# prosismic.net
KiCad netlist of a schematic drawn in EAGLE
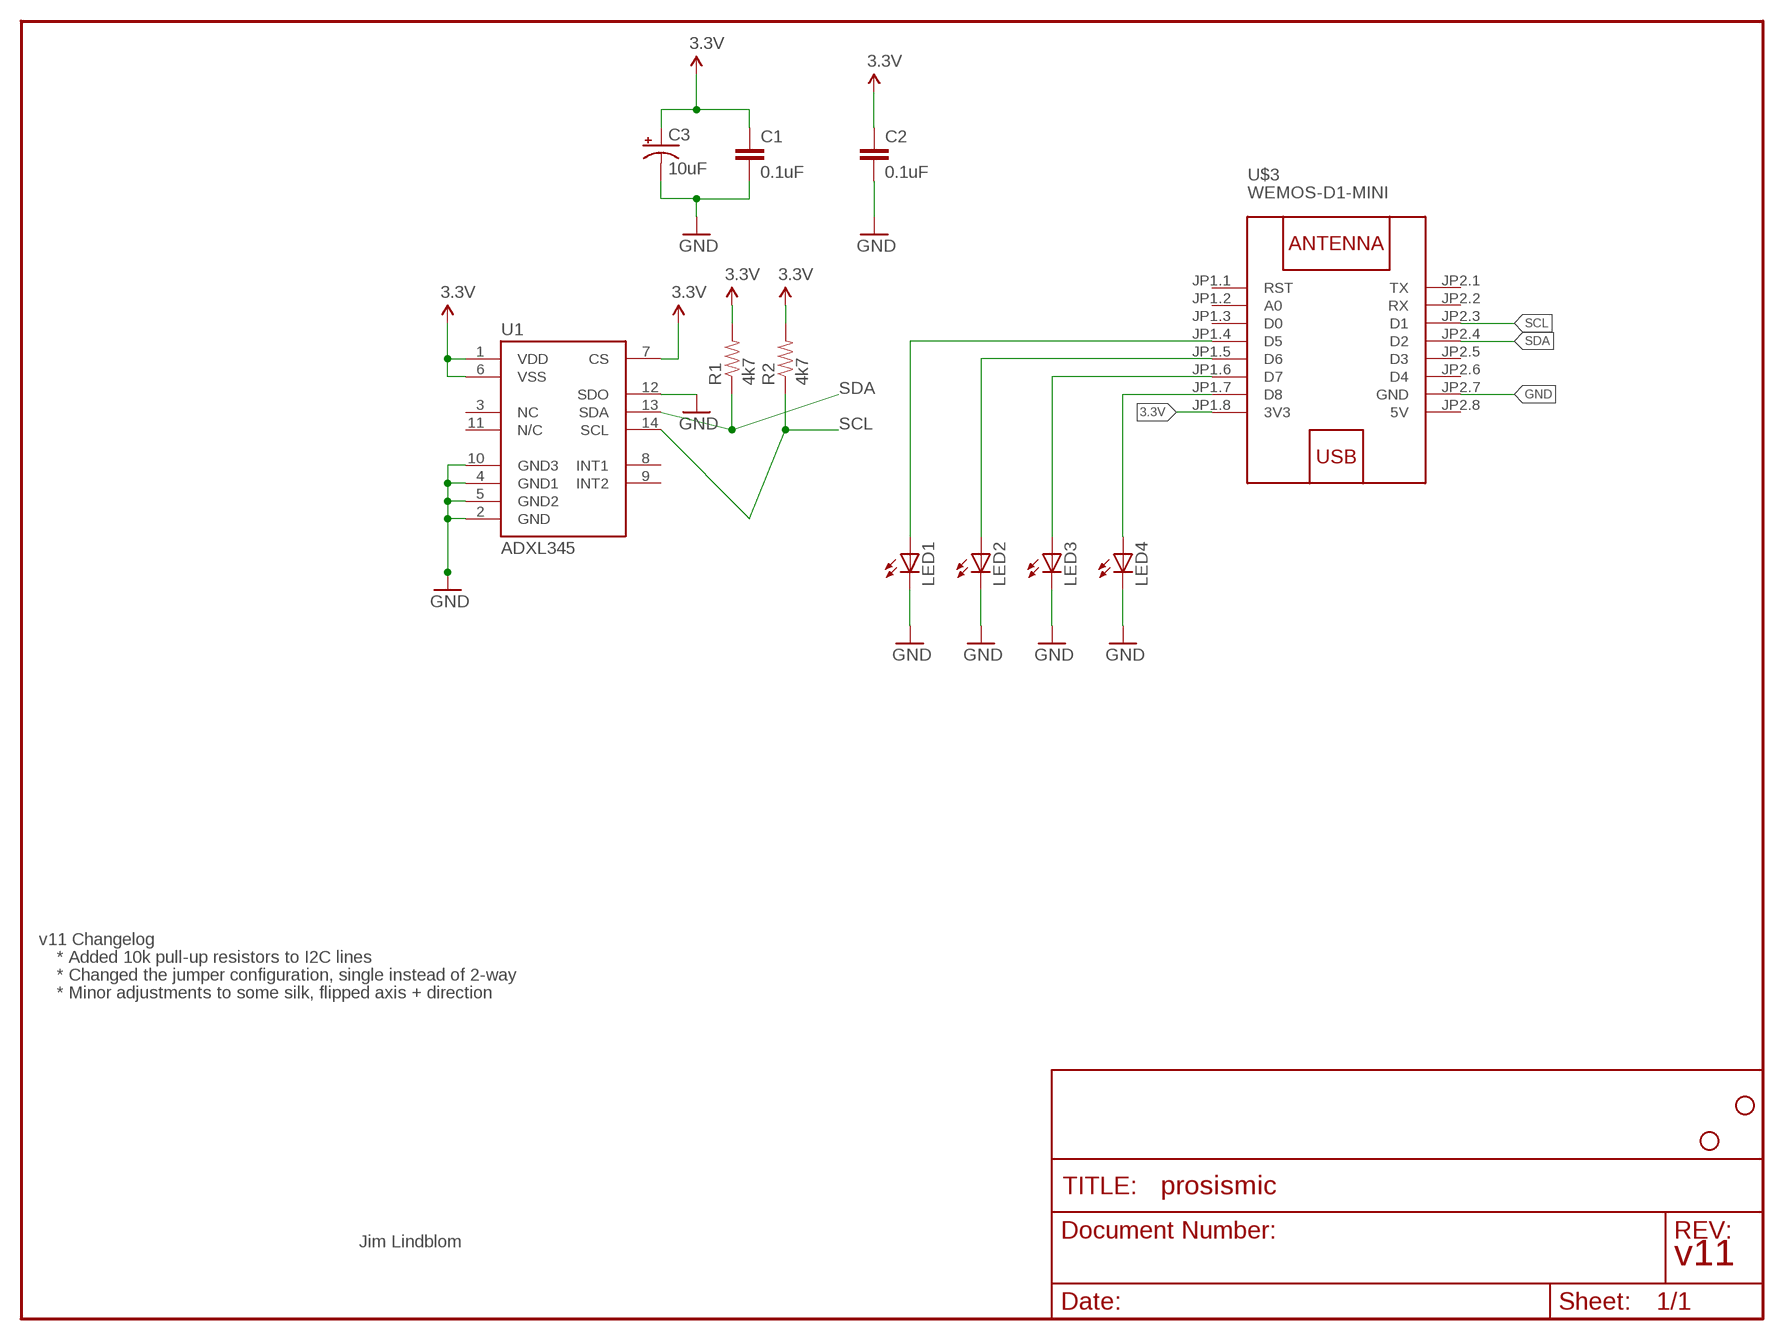
[diagram p0: schematic, sheet 1]

(export (version "E")
  (design (tool "Eeschema 10.0.6"))
  (components
    (comp (ref "C1")
      (value "0.1uF")
      (footprint "eagle-import:0402-CAP")
      (libsource (lib "eagle-import") (part "CAP0402-CAP"))
    )
    (comp (ref "C2")
      (value "0.1uF")
      (footprint "eagle-import:0402-CAP")
      (libsource (lib "eagle-import") (part "CAP0402-CAP"))
    )
    (comp (ref "C3")
      (value "10uF")
      (footprint "eagle-import:EIA3216")
      (libsource (lib "eagle-import") (part "CAP_POL1206"))
    )
    (comp (ref "JP3")
      (value "STAND-OFF")
      (footprint "eagle-import:STAND-OFF")
      (libsource (lib "eagle-import") (part "STAND-OFF"))
    )
    (comp (ref "JP4")
      (value "STAND-OFF")
      (footprint "eagle-import:STAND-OFF")
      (libsource (lib "eagle-import") (part "STAND-OFF"))
    )
    (comp (ref "LED1")
      (value "LED3MM")
      (footprint "eagle-import:LED3MM")
      (libsource (lib "eagle-import") (part "LED3MM"))
    )
    (comp (ref "LED2")
      (value "LED3MM")
      (footprint "eagle-import:LED3MM")
      (libsource (lib "eagle-import") (part "LED3MM"))
    )
    (comp (ref "LED3")
      (value "LED3MM")
      (footprint "eagle-import:LED3MM")
      (libsource (lib "eagle-import") (part "LED3MM"))
    )
    (comp (ref "LED4")
      (value "LED3MM")
      (footprint "eagle-import:LED3MM")
      (libsource (lib "eagle-import") (part "LED3MM"))
    )
    (comp (ref "R1")
      (value "4k7")
      (footprint "eagle-import:0402-RES")
      (libsource (lib "eagle-import") (part "RESISTOR0402-RES"))
    )
    (comp (ref "R2")
      (value "4k7")
      (footprint "eagle-import:0402-RES")
      (libsource (lib "eagle-import") (part "RESISTOR0402-RES"))
    )
    (comp (ref "U$3")
      (value "WEMOS-D1-MINI")
      (footprint "eagle-import:WEMOS-D1-MINI")
      (libsource (lib "eagle-import") (part "WEMOS-D1-MINI"))
    )
    (comp (ref "U1")
      (value "ADXL345")
      (footprint "eagle-import:LGA14")
      (libsource (lib "eagle-import") (part "ADXL345"))
    )
  )
  (nets
    (net (code "1") (name "/5V") (class "Default")
      (node (ref "U$3") (pin "JP2.8") (pinfunction "5V_JP2.8") (pintype "power_in"))
    )
    (net (code "2") (name "3.3V") (class "Default")
      (node (ref "C1") (pin "1") (pinfunction "1_1") (pintype "passive"))
      (node (ref "C2") (pin "1") (pinfunction "1_1") (pintype "passive"))
      (node (ref "C3") (pin "A") (pinfunction "+_A") (pintype "passive"))
      (node (ref "R1") (pin "2") (pinfunction "2_2") (pintype "passive"))
      (node (ref "R2") (pin "2") (pinfunction "2_2") (pintype "passive"))
      (node (ref "U$3") (pin "JP1.8") (pinfunction "3V3_JP1.8") (pintype "power_in"))
      (node (ref "U1") (pin "1") (pinfunction "VDD_1") (pintype "bidirectional"))
      (node (ref "U1") (pin "6") (pinfunction "VSS_6") (pintype "bidirectional"))
      (node (ref "U1") (pin "7") (pinfunction "CS_7") (pintype "bidirectional"))
    )
    (net (code "3") (name "GND") (class "Default")
      (node (ref "C1") (pin "2") (pinfunction "2_2") (pintype "passive"))
      (node (ref "C2") (pin "2") (pinfunction "2_2") (pintype "passive"))
      (node (ref "C3") (pin "C") (pinfunction "-_C") (pintype "passive"))
      (node (ref "LED1") (pin "K") (pinfunction "C_K") (pintype "passive"))
      (node (ref "LED2") (pin "K") (pinfunction "C_K") (pintype "passive"))
      (node (ref "LED3") (pin "K") (pinfunction "C_K") (pintype "passive"))
      (node (ref "LED4") (pin "K") (pinfunction "C_K") (pintype "passive"))
      (node (ref "U$3") (pin "JP2.7") (pinfunction "GND_JP2.7") (pintype "power_in"))
      (node (ref "U1") (pin "10") (pinfunction "GND3_10") (pintype "bidirectional"))
      (node (ref "U1") (pin "12") (pinfunction "SDO_12") (pintype "bidirectional"))
      (node (ref "U1") (pin "2") (pinfunction "GND_2") (pintype "bidirectional"))
      (node (ref "U1") (pin "4") (pinfunction "GND1_4") (pintype "bidirectional"))
      (node (ref "U1") (pin "5") (pinfunction "GND2_5") (pintype "bidirectional"))
    )
    (net (code "4") (name "Net-(U$3-D5)") (class "Default")
      (node (ref "LED1") (pin "A") (pinfunction "A_A") (pintype "passive"))
      (node (ref "U$3") (pin "JP1.4") (pinfunction "D5_JP1.4") (pintype "bidirectional"))
    )
    (net (code "5") (name "Net-(U$3-D6)") (class "Default")
      (node (ref "LED2") (pin "A") (pinfunction "A_A") (pintype "passive"))
      (node (ref "U$3") (pin "JP1.5") (pinfunction "D6_JP1.5") (pintype "bidirectional"))
    )
    (net (code "6") (name "Net-(U$3-D7)") (class "Default")
      (node (ref "LED3") (pin "A") (pinfunction "A_A") (pintype "passive"))
      (node (ref "U$3") (pin "JP1.6") (pinfunction "D7_JP1.6") (pintype "bidirectional"))
    )
    (net (code "7") (name "Net-(U$3-D8)") (class "Default")
      (node (ref "LED4") (pin "A") (pinfunction "A_A") (pintype "passive"))
      (node (ref "U$3") (pin "JP1.7") (pinfunction "D8_JP1.7") (pintype "bidirectional"))
    )
    (net (code "8") (name "SCL") (class "Default")
      (node (ref "R2") (pin "1") (pinfunction "1_1") (pintype "passive"))
      (node (ref "U$3") (pin "JP2.3") (pinfunction "D1_JP2.3") (pintype "bidirectional"))
      (node (ref "U1") (pin "14") (pinfunction "SCL_14") (pintype "bidirectional"))
    )
    (net (code "9") (name "SDA") (class "Default")
      (node (ref "R1") (pin "1") (pinfunction "1_1") (pintype "passive"))
      (node (ref "U$3") (pin "JP2.4") (pinfunction "D2_JP2.4") (pintype "bidirectional"))
      (node (ref "U1") (pin "13") (pinfunction "SDA_13") (pintype "bidirectional"))
    )
    (net (code "10") (name "unconnected-(U$3-A0-PadJP1.2)") (class "Default")
      (node (ref "U$3") (pin "JP1.2") (pinfunction "A0_JP1.2") (pintype "bidirectional"))
    )
    (net (code "11") (name "unconnected-(U$3-D0-PadJP1.3)") (class "Default")
      (node (ref "U$3") (pin "JP1.3") (pinfunction "D0_JP1.3") (pintype "bidirectional"))
    )
    (net (code "12") (name "unconnected-(U$3-D3-PadJP2.5)") (class "Default")
      (node (ref "U$3") (pin "JP2.5") (pinfunction "D3_JP2.5") (pintype "bidirectional"))
    )
    (net (code "13") (name "unconnected-(U$3-D4-PadJP2.6)") (class "Default")
      (node (ref "U$3") (pin "JP2.6") (pinfunction "D4_JP2.6") (pintype "bidirectional"))
    )
    (net (code "14") (name "unconnected-(U$3-RST-PadJP1.1)") (class "Default")
      (node (ref "U$3") (pin "JP1.1") (pinfunction "RST_JP1.1") (pintype "bidirectional"))
    )
    (net (code "15") (name "unconnected-(U$3-RX-PadJP2.2)") (class "Default")
      (node (ref "U$3") (pin "JP2.2") (pinfunction "RX_JP2.2") (pintype "bidirectional"))
    )
    (net (code "16") (name "unconnected-(U$3-TX-PadJP2.1)") (class "Default")
      (node (ref "U$3") (pin "JP2.1") (pinfunction "TX_JP2.1") (pintype "bidirectional"))
    )
    (net (code "17") (name "unconnected-(U1-INT1-Pad8)") (class "Default")
      (node (ref "U1") (pin "8") (pinfunction "INT1_8") (pintype "bidirectional"))
    )
    (net (code "18") (name "unconnected-(U1-INT2-Pad9)") (class "Default")
      (node (ref "U1") (pin "9") (pinfunction "INT2_9") (pintype "bidirectional"))
    )
    (net (code "19") (name "unconnected-(U1-NC-Pad3)") (class "Default")
      (node (ref "U1") (pin "3") (pinfunction "NC_3") (pintype "bidirectional"))
    )
    (net (code "20") (name "unconnected-(U1-N{slash}C-Pad11)") (class "Default")
      (node (ref "U1") (pin "11") (pinfunction "N/C_11") (pintype "bidirectional"))
    )
  )
)
